# LED_Channels.net
KiCad netlist of a schematic drawn in Altium Designer
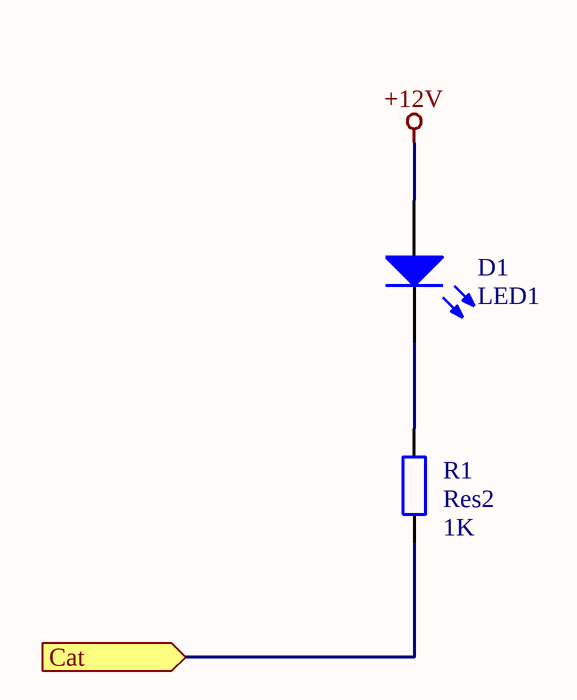
[diagram p0: LED Channels.SchDoc]

(export (version "E")
  (design (tool "Eeschema 10.0.6"))
  (components
    (comp (ref "D1")
      (value "LED1")
      (footprint "LED-1")
      (description "Typical RED GaAs LED")
      (fields (field (name "PUBLISHER") "Altium Limited"))
      (libsource (lib "Miscellaneous Devices") (part "LED1"))
    )
    (comp (ref "R1")
      (value "Res2")
      (footprint "AXIAL-0.4")
      (description "Resistor")
      (fields (field (name "ALTIUM_VALUE") "1K") (field (name "PUBLISHER") "Altium Limited"))
      (libsource (lib "Miscellaneous Devices") (part "Res2"))
    )
  )
  (nets
    (net (code "1") (name "+12V") (class "Default")
      (node (ref "D1") (pin "1") (pinfunction "A_1") (pintype "passive"))
    )
    (net (code "2") (name "/Cat") (class "Default")
      (node (ref "R1") (pin "1") (pinfunction "1_1") (pintype "passive"))
    )
    (net (code "3") (name "Net-(D1-K)") (class "Default")
      (node (ref "D1") (pin "2") (pinfunction "K_2") (pintype "passive"))
      (node (ref "R1") (pin "2") (pinfunction "2_2") (pintype "passive"))
    )
  )
)
